# Car_Power_Supply_v2.net
KiCad netlist of a schematic drawn in Altium Designer
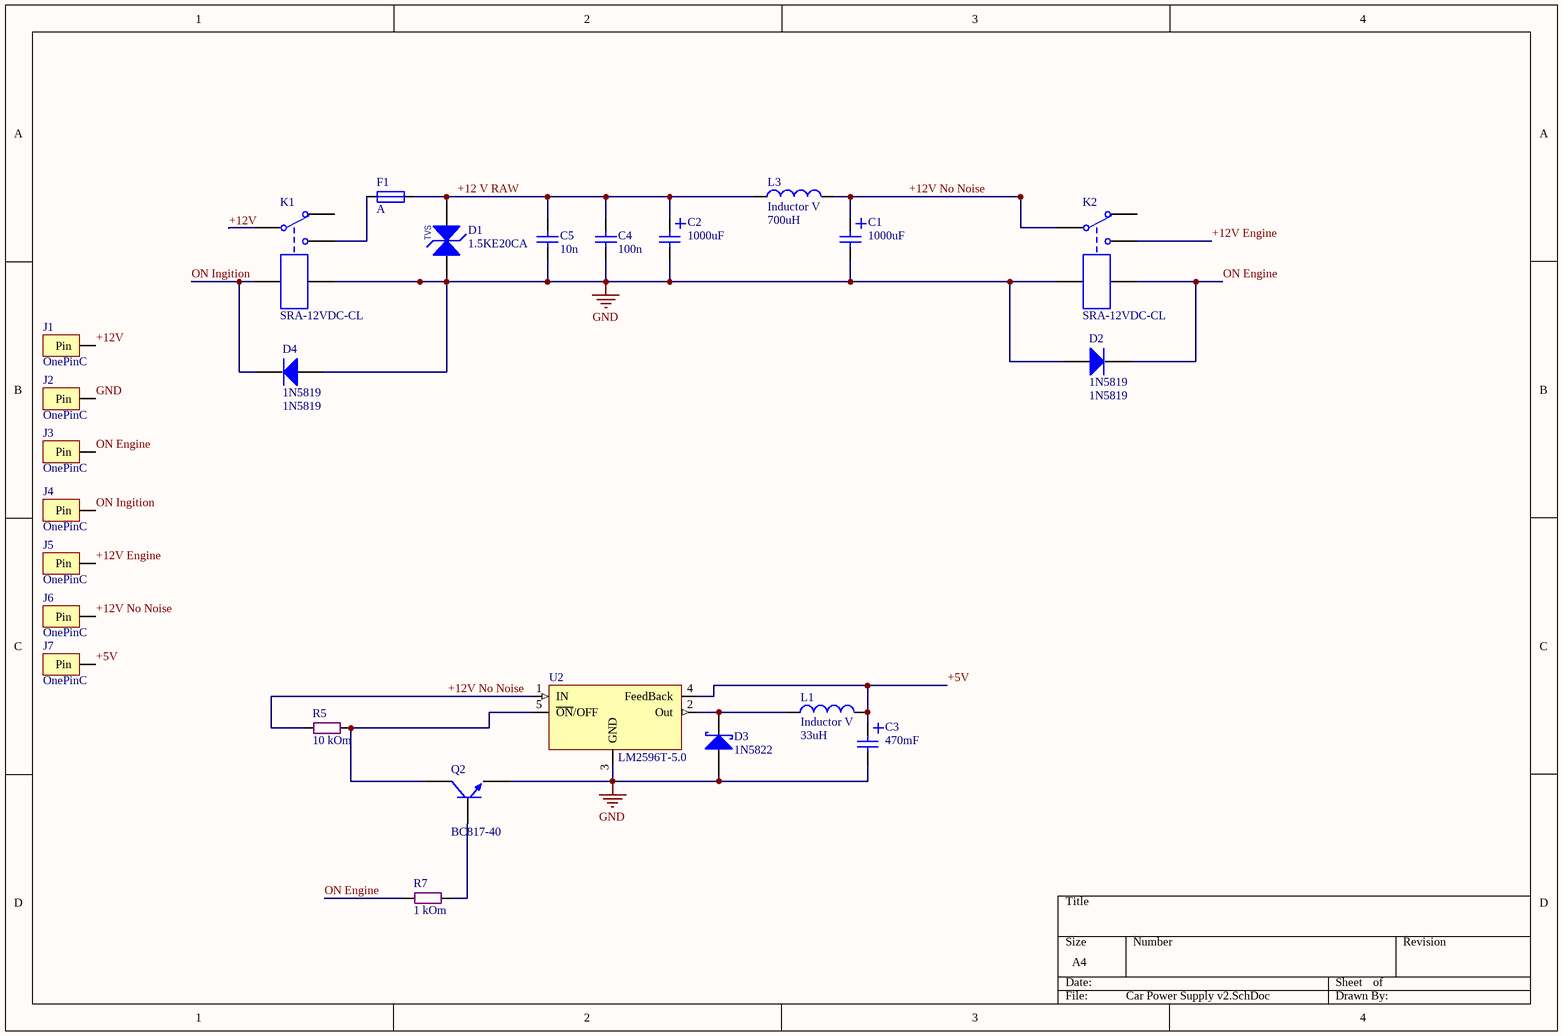
[diagram p0: Car Power Supply v2.SchDoc]

(export (version "E")
  (design (tool "Eeschema 10.0.6"))
  (components
    (comp (ref "C1")
      (value "1000uF")
      (footprint "Capacitor:Cap E p5.08mm D10.2mm (3p)")
      (description "Capacitor")
      (libsource (lib "Capacitor") (part "Cap E 1000mF x 25V"))
    )
    (comp (ref "C2")
      (value "1000uF")
      (footprint "Capacitor:Cap E p5.08mm D10.2mm (3p)")
      (description "Capacitor")
      (libsource (lib "Capacitor") (part "Cap E 1000mF x 25V"))
    )
    (comp (ref "C3")
      (value "470mF")
      (footprint "Capacitor:Cap E p5.08mm D10.2mm (3p)")
      (description "Capacitor")
      (libsource (lib "Capacitor") (part "Cap E 1000mF x 25V"))
    )
    (comp (ref "C4")
      (value "100n")
      (footprint "Capacitor:Cap P5.08MM (3p) disk2")
      (description "Capacitor")
      (libsource (lib "Capacitor") (part "Cap Ceramic"))
    )
    (comp (ref "C5")
      (value "10n")
      (footprint "Capacitor:Cap P5.08MM (3p) disk2")
      (description "Capacitor")
      (libsource (lib "Capacitor") (part "Cap Ceramic"))
    )
    (comp (ref "D1")
      (value "1.5KE20CA")
      (footprint "Diodes:TVS diode DO-201 V")
      (description "1500W Transil (TVS Diode)")
      (libsource (lib "Diodes") (part "TVS 1.5KE20CA"))
    )
    (comp (ref "D2")
      (value "1N5819")
      (footprint "Diodes:Diode DO-35")
      (description "1 Amp General Purpose Rectifier")
      (fields (field (name "ALTIUM_VALUE") "1N5819"))
      (libsource (lib "Diodes") (part "Diode 1N5819"))
    )
    (comp (ref "D3")
      (value "1N5822")
      (footprint "Diodes:Diode DO-201 V")
      (description "3 Amp Shotki  Diode")
      (libsource (lib "Diodes") (part "D Shotki 1N5822"))
    )
    (comp (ref "D4")
      (value "1N5819")
      (footprint "Diodes:Diode DO-35")
      (description "1 Amp General Purpose Rectifier")
      (fields (field (name "ALTIUM_VALUE") "1N5819"))
      (libsource (lib "Diodes") (part "Diode 1N5819"))
    )
    (comp (ref "F1")
      (value "A")
      (footprint "PassiveComponents:Fuse RGE1100")
      (description "Round fuse")
      (libsource (lib "PassiveComponents") (part "Fuse"))
    )
    (comp (ref "J1")
      (value "OnePinC")
      (footprint "Connector:OnePin 1.2x3")
      (description "Only pad")
      (libsource (lib "Connector") (part "OnePin Connector"))
    )
    (comp (ref "J2")
      (value "OnePinC")
      (footprint "Connector:OnePin 1.2x3")
      (description "Only pad")
      (libsource (lib "Connector") (part "OnePin Connector"))
    )
    (comp (ref "J3")
      (value "OnePinC")
      (footprint "Connector:OnePin 1.2x3")
      (description "Only pad")
      (libsource (lib "Connector") (part "OnePin Connector"))
    )
    (comp (ref "J4")
      (value "OnePinC")
      (footprint "Connector:OnePin 1.2x3")
      (description "Only pad")
      (libsource (lib "Connector") (part "OnePin Connector"))
    )
    (comp (ref "J5")
      (value "OnePinC")
      (footprint "Connector:OnePin 1.2x3")
      (description "Only pad")
      (libsource (lib "Connector") (part "OnePin Connector"))
    )
    (comp (ref "J6")
      (value "OnePinC")
      (footprint "Connector:OnePin 1.2x3")
      (description "Only pad")
      (libsource (lib "Connector") (part "OnePin Connector"))
    )
    (comp (ref "J7")
      (value "OnePinC")
      (footprint "Connector:OnePin 1.2x3")
      (description "Only pad")
      (libsource (lib "Connector") (part "OnePin Connector"))
    )
    (comp (ref "K1")
      (value "SRA-12VDC-CL")
      (footprint "Relay:SRA-12VDC-CL")
      (description "Single-Pole Dual-Throw Relay")
      (libsource (lib "Relay") (part "SRA-12VDC-CL"))
    )
    (comp (ref "K2")
      (value "SRA-12VDC-CL")
      (footprint "Relay:SRA-12VDC-CL")
      (description "Single-Pole Dual-Throw Relay")
      (libsource (lib "Relay") (part "SRA-12VDC-CL"))
    )
    (comp (ref "L1")
      (value "Inductor V")
      (footprint "Transformers:Toroid V D14-W6")
      (description "Inductor Vertical")
      (fields (field (name "ALTIUM_VALUE") "33uH") (field (name "PUBLISHER") "Altium Limited"))
      (libsource (lib "Transformers") (part "Inductor V"))
    )
    (comp (ref "L3")
      (value "Inductor V")
      (footprint "Transformers:Toroid V D14-W6")
      (description "Inductor Vertical")
      (fields (field (name "ALTIUM_VALUE") "700uH") (field (name "PUBLISHER") "Altium Limited"))
      (libsource (lib "Transformers") (part "Inductor V"))
    )
    (comp (ref "Q2")
      (value "BC817-40")
      (footprint "GeneralCases:SOT-23")
      (description "NPN 45 V, 500 mA NPN general-purpose transistor")
      (libsource (lib "Transistor") (part "BC817-40"))
    )
    (comp (ref "R5")
      (value "10 kOm")
      (footprint "PassiveComponents:Res p7.62 (4p) 0.25w")
      (libsource (lib "PassiveComponents") (part "Res All Types"))
    )
    (comp (ref "R7")
      (value "1 kOm")
      (footprint "PassiveComponents:Res p7.62 (4p) 0.25w")
      (libsource (lib "PassiveComponents") (part "Res All Types"))
    )
    (comp (ref "U2")
      (value "LM2596T-5.0")
      (footprint "GeneralCases:TO220-5 Vertical")
      (description "Voltage Regulator")
      (fields (field (name "MANUFACTURER") "National Semiconductor"))
      (libsource (lib "PowerAdjusment") (part "LM2596T-5.0"))
    )
  )
  (nets
    (net (code "1") (name "/+5V") (class "Default")
      (node (ref "C3") (pin "1") (pinfunction "1_1") (pintype "passive"))
      (node (ref "J7") (pin "1") (pinfunction "Pin_1") (pintype "passive"))
      (node (ref "L1") (pin "2") (pinfunction "2_2") (pintype "passive"))
      (node (ref "U2") (pin "4") (pinfunction "FeedBack_4") (pintype "passive"))
    )
    (net (code "2") (name "/+12 V RAW") (class "Default")
      (node (ref "C2") (pin "1") (pinfunction "1_1") (pintype "passive"))
      (node (ref "C4") (pin "1") (pinfunction "1_1") (pintype "passive"))
      (node (ref "C5") (pin "1") (pinfunction "1_1") (pintype "passive"))
      (node (ref "D1") (pin "2") (pinfunction "2_2") (pintype "passive"))
      (node (ref "F1") (pin "2") (pinfunction "2_2") (pintype "passive"))
      (node (ref "L3") (pin "1") (pinfunction "1_1") (pintype "passive"))
    )
    (net (code "3") (name "/+12V") (class "Default")
      (node (ref "J1") (pin "1") (pinfunction "Pin_1") (pintype "passive"))
      (node (ref "K1") (pin "2") (pinfunction "2_2") (pintype "passive"))
    )
    (net (code "4") (name "/+12V Engine") (class "Default")
      (node (ref "J5") (pin "1") (pinfunction "Pin_1") (pintype "passive"))
      (node (ref "K2") (pin "3") (pinfunction "3_3") (pintype "passive"))
    )
    (net (code "5") (name "/+12V No Noise") (class "Default")
      (node (ref "C1") (pin "1") (pinfunction "1_1") (pintype "passive"))
      (node (ref "J6") (pin "1") (pinfunction "Pin_1") (pintype "passive"))
      (node (ref "K2") (pin "2") (pinfunction "2_2") (pintype "passive"))
      (node (ref "L3") (pin "2") (pinfunction "2_2") (pintype "passive"))
      (node (ref "R5") (pin "1") (pinfunction "1_1") (pintype "passive"))
      (node (ref "U2") (pin "1") (pinfunction "IN_1") (pintype "input"))
    )
    (net (code "6") (name "/ON Engine") (class "Default")
      (node (ref "D2") (pin "K") (pinfunction "K_K") (pintype "passive"))
      (node (ref "J3") (pin "1") (pinfunction "Pin_1") (pintype "passive"))
      (node (ref "K2") (pin "5") (pinfunction "5_5") (pintype "passive"))
      (node (ref "R7") (pin "1") (pinfunction "1_1") (pintype "passive"))
    )
    (net (code "7") (name "/ON Ingition") (class "Default")
      (node (ref "D4") (pin "K") (pinfunction "K_K") (pintype "passive"))
      (node (ref "J4") (pin "1") (pinfunction "Pin_1") (pintype "passive"))
      (node (ref "K1") (pin "4") (pinfunction "4_4") (pintype "passive"))
    )
    (net (code "8") (name "GND") (class "Default")
      (node (ref "C1") (pin "2") (pinfunction "2_2") (pintype "passive"))
      (node (ref "C2") (pin "2") (pinfunction "2_2") (pintype "passive"))
      (node (ref "C3") (pin "2") (pinfunction "2_2") (pintype "passive"))
      (node (ref "C4") (pin "2") (pinfunction "2_2") (pintype "passive"))
      (node (ref "C5") (pin "2") (pinfunction "2_2") (pintype "passive"))
      (node (ref "D1") (pin "1") (pinfunction "1_1") (pintype "passive"))
      (node (ref "D2") (pin "A") (pinfunction "A_A") (pintype "passive"))
      (node (ref "D3") (pin "A") (pinfunction "A_A") (pintype "passive"))
      (node (ref "D4") (pin "A") (pinfunction "A_A") (pintype "passive"))
      (node (ref "J2") (pin "1") (pinfunction "Pin_1") (pintype "passive"))
      (node (ref "K1") (pin "5") (pinfunction "5_5") (pintype "passive"))
      (node (ref "K2") (pin "4") (pinfunction "4_4") (pintype "passive"))
      (node (ref "Q2") (pin "2") (pinfunction "E_2") (pintype "passive"))
      (node (ref "U2") (pin "3") (pinfunction "GND_3") (pintype "passive"))
    )
    (net (code "9") (name "Net-(F1-Pad1)") (class "Default")
      (node (ref "F1") (pin "1") (pinfunction "1_1") (pintype "passive"))
      (node (ref "K1") (pin "3") (pinfunction "3_3") (pintype "passive"))
    )
    (net (code "10") (name "Net-(Q2-B)") (class "Default")
      (node (ref "Q2") (pin "1") (pinfunction "B_1") (pintype "passive"))
      (node (ref "R7") (pin "2") (pinfunction "2_2") (pintype "passive"))
    )
    (net (code "11") (name "Net-(Q2-C)") (class "Default")
      (node (ref "Q2") (pin "3") (pinfunction "C_3") (pintype "passive"))
      (node (ref "R5") (pin "2") (pinfunction "2_2") (pintype "passive"))
      (node (ref "U2") (pin "5") (pinfunction "~{ON}/OFF_5") (pintype "passive"))
    )
    (net (code "12") (name "Net-(U2-Out)") (class "Default")
      (node (ref "D3") (pin "K") (pinfunction "K_K") (pintype "passive"))
      (node (ref "L1") (pin "1") (pinfunction "1_1") (pintype "passive"))
      (node (ref "U2") (pin "2") (pinfunction "Out_2") (pintype "output"))
    )
    (net (code "13") (name "unconnected-(K1-Pad1)") (class "Default")
      (node (ref "K1") (pin "1") (pinfunction "1_1") (pintype "passive"))
    )
    (net (code "14") (name "unconnected-(K2-Pad1)") (class "Default")
      (node (ref "K2") (pin "1") (pinfunction "1_1") (pintype "passive"))
    )
  )
)
